# memory.net
KiCad netlist of a schematic drawn in Altium Designer
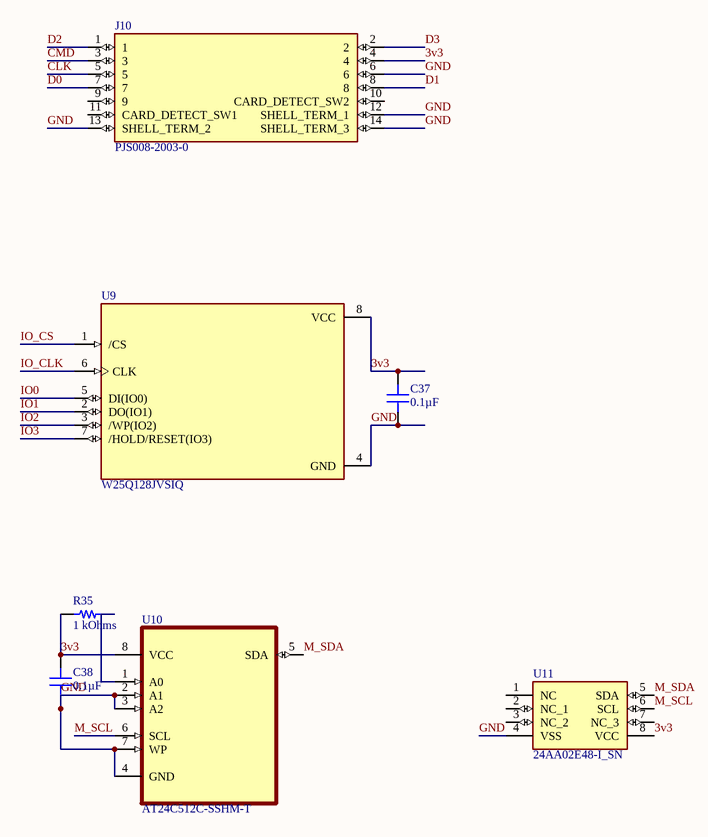
[diagram p0: memory.SchDoc]

(export (version "E")
  (design (tool "Eeschema 10.0.6"))
  (components
    (comp (ref "C37")
      (value "1µF")
      (footprint "CAP 0805_2012")
      (description "CAP CER 1UF 10V X7R 0805")
      (fields
        (field (name "PART NUMBER") "0805ZC105KAT4A")
        (field (name "CAPACITANCE") "0.1µF")
        (field (name "MANUFACTURER") "AVX Corporation")
      )
      (libsource (lib "Celestial Altium Library - altium_library") (part "Capacitor"))
    )
    (comp (ref "C38")
      (value "1µF")
      (footprint "CAP 0805_2012")
      (description "CAP CER 1UF 10V X7R 0805")
      (fields
        (field (name "PART NUMBER") "0805ZC105KAT4A")
        (field (name "CAPACITANCE") "0.1µF")
        (field (name "MANUFACTURER") "AVX Corporation")
      )
      (libsource (lib "Celestial Altium Library - altium_library") (part "Capacitor"))
    )
    (comp (ref "J10")
      (value "PJS008-2003-0")
      (footprint "PJS008-2003-0")
      (description "Memory Card Connectors MicroSD Crd Conn SMT Revrs Mnt Push-Push")
      (fields (field (name "MF") "Yamaichi Electronics"))
      (libsource (lib "PJS008-2003-0") (part "PJS008-2003-0"))
    )
    (comp (ref "R35")
      (value "1 kOhms")
      (footprint "RES 0805_2012")
      (description "RES SMD 1K OHM 1% 0.4W 0805")
      (fields (field (name "PART NUMBER") "ESR10EZPF1001") (field (name "MANUFACTURER") "Rohm Semiconductor"))
      (libsource (lib "Celestial Altium Library - altium_library") (part "Resistor"))
    )
    (comp (ref "U9")
      (value "W25Q128JVSIQ")
      (footprint "SOIC127P790X216-8N")
      (description "FLASH - NOR Memory IC 128Mb (16M x 8) SPI - Quad I/O, QPI, DTR 133 MHz 8-SOIC")
      (fields (field (name "MF") "Winbond Electronics"))
      (libsource (lib "W25Q128JVSIQ") (part "W25Q128JVSIQ"))
    )
    (comp (ref "U10")
      (value "AT24C512C-SSHM-T")
      (footprint "SOIC127P600X175-8N")
      (description "EEPROM Memory IC 512Kb (64K x 8) IÂ²C 400 kHz 900 ns 8-SOIC")
      (fields (field (name "MF") "Microchip"))
      (libsource (lib "AT24C512C-SSHM-T") (part "AT24C512C-SSHM-T"))
    )
    (comp (ref "U11")
      (value "24AA02E48-I_SN")
      (footprint "SOIC127P600X175-8N")
      (fields (field (name "MF") "Microchip") (field (name "MP") "24AA02E48-I/SN"))
      (libsource (lib "24AA02E48-I_SN") (part "24AA02E48-I_SN"))
    )
  )
  (nets
    (net (code "1") (name "/3v3") (class "Default")
      (node (ref "C37") (pin "2") (pinfunction "2_2") (pintype "passive"))
      (node (ref "C38") (pin "2") (pinfunction "2_2") (pintype "passive"))
      (node (ref "J10") (pin "4") (pinfunction "4_4") (pintype "bidirectional"))
      (node (ref "R35") (pin "1") (pinfunction "1_1") (pintype "passive"))
      (node (ref "U10") (pin "8") (pinfunction "VCC_8") (pintype "power_in"))
      (node (ref "U11") (pin "8") (pinfunction "VCC_8") (pintype "power_in"))
      (node (ref "U9") (pin "8") (pinfunction "VCC_8") (pintype "power_in"))
    )
    (net (code "2") (name "/CLK") (class "Default")
      (node (ref "J10") (pin "5") (pinfunction "5_5") (pintype "bidirectional"))
    )
    (net (code "3") (name "/CMD") (class "Default")
      (node (ref "J10") (pin "3") (pinfunction "3_3") (pintype "bidirectional"))
    )
    (net (code "4") (name "/D0") (class "Default")
      (node (ref "J10") (pin "7") (pinfunction "7_7") (pintype "bidirectional"))
    )
    (net (code "5") (name "/D1") (class "Default")
      (node (ref "J10") (pin "8") (pinfunction "8_8") (pintype "bidirectional"))
    )
    (net (code "6") (name "/D2") (class "Default")
      (node (ref "J10") (pin "1") (pinfunction "1_1") (pintype "bidirectional"))
    )
    (net (code "7") (name "/D3") (class "Default")
      (node (ref "J10") (pin "2") (pinfunction "2_2") (pintype "bidirectional"))
    )
    (net (code "8") (name "/GND") (class "Default")
      (node (ref "C37") (pin "1") (pinfunction "1_1") (pintype "passive"))
      (node (ref "C38") (pin "1") (pinfunction "1_1") (pintype "passive"))
      (node (ref "J10") (pin "12") (pinfunction "SHELL_TERM_1_12") (pintype "bidirectional"))
      (node (ref "J10") (pin "13") (pinfunction "SHELL_TERM_2_13") (pintype "bidirectional"))
      (node (ref "J10") (pin "14") (pinfunction "SHELL_TERM_3_14") (pintype "bidirectional"))
      (node (ref "J10") (pin "6") (pinfunction "6_6") (pintype "bidirectional"))
      (node (ref "U10") (pin "2") (pinfunction "A1_2") (pintype "input"))
      (node (ref "U10") (pin "3") (pinfunction "A2_3") (pintype "input"))
      (node (ref "U10") (pin "4") (pinfunction "GND_4") (pintype "passive"))
      (node (ref "U10") (pin "7") (pinfunction "WP_7") (pintype "input"))
      (node (ref "U11") (pin "4") (pinfunction "VSS_4") (pintype "power_in"))
      (node (ref "U9") (pin "4") (pinfunction "GND_4") (pintype "power_in"))
    )
    (net (code "9") (name "/IO0") (class "Default")
      (node (ref "U9") (pin "5") (pinfunction "DI(IO0)_5") (pintype "bidirectional"))
    )
    (net (code "10") (name "/IO1") (class "Default")
      (node (ref "U9") (pin "2") (pinfunction "DO(IO1)_2") (pintype "bidirectional"))
    )
    (net (code "11") (name "/IO2") (class "Default")
      (node (ref "U9") (pin "3") (pinfunction "/WP(IO2)_3") (pintype "bidirectional"))
    )
    (net (code "12") (name "/IO3") (class "Default")
      (node (ref "U9") (pin "7") (pinfunction "/HOLD/RESET(IO3)_7") (pintype "bidirectional"))
    )
    (net (code "13") (name "/IO_CLK") (class "Default")
      (node (ref "U9") (pin "6") (pinfunction "CLK_6") (pintype "input"))
    )
    (net (code "14") (name "/IO_CS") (class "Default")
      (node (ref "U9") (pin "1") (pinfunction "/CS_1") (pintype "input"))
    )
    (net (code "15") (name "/M_SCL") (class "Default")
      (node (ref "U10") (pin "6") (pinfunction "SCL_6") (pintype "input"))
      (node (ref "U11") (pin "6") (pinfunction "SCL_6") (pintype "bidirectional"))
    )
    (net (code "16") (name "/M_SDA") (class "Default")
      (node (ref "U10") (pin "5") (pinfunction "SDA_5") (pintype "bidirectional"))
      (node (ref "U11") (pin "5") (pinfunction "SDA_5") (pintype "bidirectional"))
    )
    (net (code "17") (name "Net-(U10-A0)") (class "Default")
      (node (ref "R35") (pin "2") (pinfunction "2_2") (pintype "passive"))
      (node (ref "U10") (pin "1") (pinfunction "A0_1") (pintype "input"))
    )
    (net (code "18") (name "unconnected-(J10-CARD_DETECT_SW1-Pad11)") (class "Default")
      (node (ref "J10") (pin "11") (pinfunction "CARD_DETECT_SW1_11") (pintype "bidirectional"))
    )
    (net (code "19") (name "unconnected-(J10-CARD_DETECT_SW2-Pad10)") (class "Default")
      (node (ref "J10") (pin "10") (pinfunction "CARD_DETECT_SW2_10") (pintype "bidirectional"))
    )
    (net (code "20") (name "unconnected-(J10-Pad9)") (class "Default")
      (node (ref "J10") (pin "9") (pinfunction "9_9") (pintype "bidirectional"))
    )
    (net (code "21") (name "unconnected-(U11-NC-Pad1)") (class "Default")
      (node (ref "U11") (pin "1") (pinfunction "NC_1") (pintype "passive"))
    )
    (net (code "22") (name "unconnected-(U11-NC_1-Pad2)") (class "Default")
      (node (ref "U11") (pin "2") (pinfunction "NC_1_2") (pintype "bidirectional"))
    )
    (net (code "23") (name "unconnected-(U11-NC_2-Pad3)") (class "Default")
      (node (ref "U11") (pin "3") (pinfunction "NC_2_3") (pintype "bidirectional"))
    )
    (net (code "24") (name "unconnected-(U11-NC_3-Pad7)") (class "Default")
      (node (ref "U11") (pin "7") (pinfunction "NC_3_7") (pintype "bidirectional"))
    )
  )
)
